# Power.net
KiCad netlist of a schematic drawn in Altium Designer
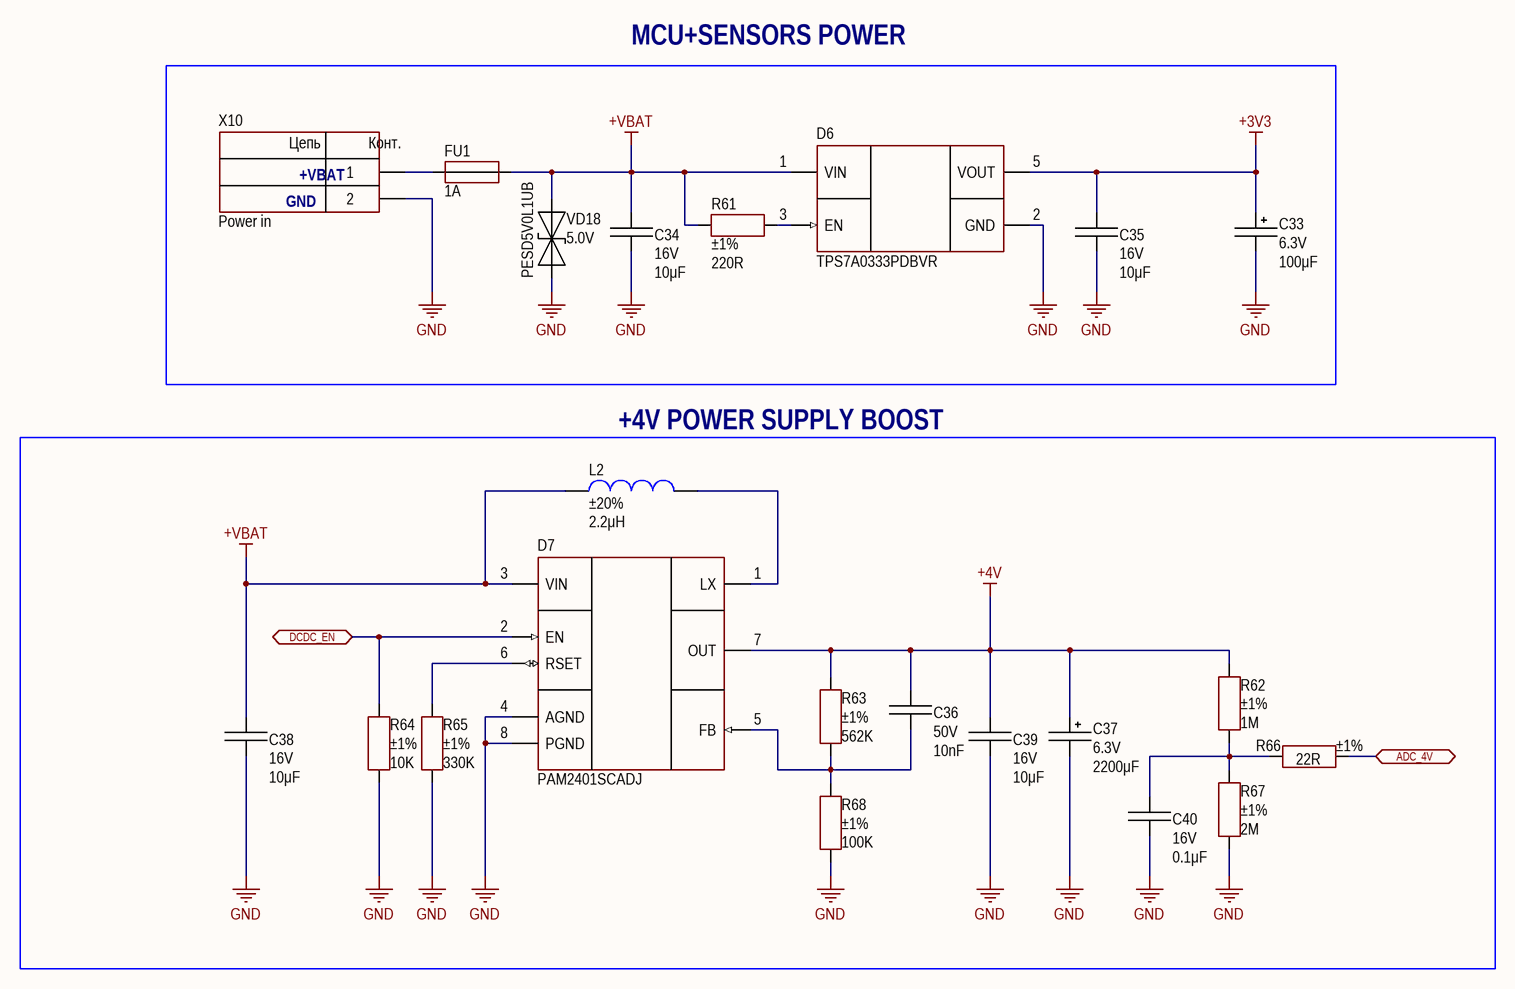
[diagram p0: Power.SchDoc]

(export (version "E")
  (design (tool "Eeschema 10.0.6"))
  (components
    (comp (ref "C33")
      (value "100μF")
      (footprint "CAP: TANTAL-A")
      (description "100 µF Molded Tantalum Polymer Capacitor 6.3 V 1206 (3216 Metric) 100mOhm @ 100kHz")
      (fields
        (field (name "MANUFACTURER") "AVX")
        (field (name "PARTNUMBER") "TCJA107M006R0100")
        (field (name "VOLTAGE") "6.3V")
      )
      (libsource (lib "capacitor") (part "Tantal_A"))
    )
    (comp (ref "C34")
      (value "10μF")
      (footprint "CAP: 0805")
      (description "±20% 16V Ceramic Capacitor X7R 0805 (2012 Metric)")
      (fields
        (field (name "MANUFACTURER") "Yageo")
        (field (name "PARTNUMBER") "CC0805MKX7R7BB106")
        (field (name "VOLTAGE") "16V")
      )
      (libsource (lib "capacitor") (part "Ceramic_0805"))
    )
    (comp (ref "C35")
      (value "10μF")
      (footprint "CAP: 0805")
      (description "±20% 16V Ceramic Capacitor X7R 0805 (2012 Metric)")
      (fields
        (field (name "MANUFACTURER") "Yageo")
        (field (name "PARTNUMBER") "CC0805MKX7R7BB106")
        (field (name "VOLTAGE") "16V")
      )
      (libsource (lib "capacitor") (part "Ceramic_0805"))
    )
    (comp (ref "C36")
      (value "10nF")
      (footprint "CAP: 0402")
      (description "10000 pF ±10% 50V Ceramic Capacitor X7R 0402 (1005 Metric)")
      (fields
        (field (name "MANUFACTURER") "Yageo")
        (field (name "PARTNUMBER") "CC0402KRX7R9BB103")
        (field (name "VOLTAGE") "50V")
      )
      (libsource (lib "capacitor") (part "Ceramic_0402"))
    )
    (comp (ref "C37")
      (value "2200μF")
      (footprint "CAP: D10C5H12.5")
      (description "2200 µF 6.3 V Aluminum - Polymer Capacitors Radial, Can 13mOhm 2000 Hrs @ 125°C")
      (fields
        (field (name "MANUFACTURER") "KEMET")
        (field (name "PARTNUMBER") "A759MS228M0JAAE013")
        (field (name "VOLTAGE") "6.3V")
      )
      (libsource (lib "capacitor") (part "Aluminium"))
    )
    (comp (ref "C38")
      (value "10μF")
      (footprint "CAP: 0805")
      (description "±20% 16V Ceramic Capacitor X7R 0805 (2012 Metric)")
      (fields
        (field (name "MANUFACTURER") "Yageo")
        (field (name "PARTNUMBER") "CC0805MKX7R7BB106")
        (field (name "VOLTAGE") "16V")
      )
      (libsource (lib "capacitor") (part "Ceramic_0805"))
    )
    (comp (ref "C39")
      (value "10μF")
      (footprint "CAP: 0805")
      (description "±20% 16V Ceramic Capacitor X7R 0805 (2012 Metric)")
      (fields
        (field (name "MANUFACTURER") "Yageo")
        (field (name "PARTNUMBER") "CC0805MKX7R7BB106")
        (field (name "VOLTAGE") "16V")
      )
      (libsource (lib "capacitor") (part "Ceramic_0805"))
    )
    (comp (ref "C40")
      (value "0.1μF")
      (footprint "CAP: 0402")
      (description "±10% 16V Ceramic Capacitor X7R 0402 (1005 Metric)")
      (fields
        (field (name "MANUFACTURER") "Yageo")
        (field (name "PARTNUMBER") "CC0402KRX7R7BB104")
        (field (name "VOLTAGE") "16V")
      )
      (libsource (lib "capacitor") (part "Ceramic_0402"))
    )
    (comp (ref "D6")
      (value "~")
      (footprint "SOT23-5")
      (description "Linear Voltage Regulator IC Positive Fixed 1 Output 3.3V 200mA SOT-23-5")
      (fields
        (field (name "MANUFACTURER") "Texas Instruments")
        (field (name "VALUEMANUFACTURERPARTNUMBER") "Linear voltage regulator, input 3.2...6V, 0.27V, output 3.3V, 0.2A, -40...+85°C, SOT23-6")
        (field (name "PARTNUMBER") "TPS7A0333PDBVR")
      )
      (libsource (lib "ic-power-supply") (part "AP2204K-3.3TRG1"))
    )
    (comp (ref "D7")
      (value "~")
      (footprint "8-TSSOP")
      (fields
        (field (name "MANUFACTURER") "Diodes Incorporated")
        (field (name "VALUEMANUFACTURERPARTNUMBER") "DC/DC boost converter, input 0.9...4.75V, 1MHz, output 2.5..5V, 1A, -40...+125°C, TO-263-5")
        (field (name "PARTNUMBER") "PAM2401SCADJ")
      )
      (libsource (lib "MyLib") (part "PAM2401SCADJ"))
    )
    (comp (ref "FU1")
      (value "~")
      (footprint "FUSE: 1206")
      (description "Polymeric PTC Resettable Fuse 6V 1 A Ih Surface Mount 1206 (3216 Metric), Concave")
      (fields
        (field (name "MANUFACTURER") "Bel Fuse Inc.")
        (field (name "VALUEMANUFACTURERPARTNUMBER") "Electromechanics relay, 6V, 1A, 1206, ")
        (field (name "MAXCURRENT") "1A")
      )
      (libsource (lib "electromechanics") (part "Fuse"))
    )
    (comp (ref "L2")
      (value "2.2μH")
      (footprint "IND: 1008 (2520)")
      (description "2.2 µH Shielded Multilayer Inductor 1.3 A 80mOhm Max 1008 (2520 Metric)")
      (fields
        (field (name "MANUFACTURER") "Bourns")
        (field (name "PARTNUMBER") "CVH252009-2R2M")
        (field (name "TOLERANCE") "±20%")
      )
      (libsource (lib "MyLib") (part "Inductor_1008 (2520)"))
    )
    (comp (ref "R61")
      (value "220R")
      (footprint "RES: 0402")
      (description "220 Ohms ±1% 0.063W, 1/16W Chip Resistor 0402 (1005 Metric) Moisture Resistant Thick Film")
      (fields
        (field (name "MANUFACTURER") "Yageo")
        (field (name "PARTNUMBER") "RC0402FR-07220RL")
        (field (name "TOLERANCE") "±1%")
      )
      (libsource (lib "") (part "Resistor_0402_2"))
    )
    (comp (ref "R62")
      (value "1M")
      (footprint "RES: 0402")
      (description "1 MOhms ±1% 0.063W, 1/16W Chip Resistor 0402 (1005 Metric) Moisture Resistant Thick Film")
      (fields
        (field (name "MANUFACTURER") "Yageo")
        (field (name "PARTNUMBER") "RC0402FR-071ML")
        (field (name "TOLERANCE") "±1%")
      )
      (libsource (lib "") (part "Resistor_0402_1"))
    )
    (comp (ref "R63")
      (value "562K")
      (footprint "RES: 0402")
      (description "562 kOhms ±1% 0.063W, 1/16W Chip Resistor 0402 (1005 Metric) Moisture Resistant Thick Film")
      (fields
        (field (name "MANUFACTURER") "Yageo")
        (field (name "PARTNUMBER") "RC0402FR-07562KL")
        (field (name "TOLERANCE") "±1%")
      )
      (libsource (lib "resistor") (part "Resistor_0402"))
    )
    (comp (ref "R64")
      (value "10K")
      (footprint "RES: 0402")
      (description "10 kOhms ±1% 0.063W, 1/16W Chip Resistor 0402 (1005 Metric) Moisture Resistant Thick Film")
      (fields
        (field (name "MANUFACTURER") "Yageo")
        (field (name "PARTNUMBER") "RC0402FR-0710KL")
        (field (name "TOLERANCE") "±1%")
      )
      (libsource (lib "resistor") (part "Resistor_0402"))
    )
    (comp (ref "R65")
      (value "330K")
      (footprint "RES: 0402")
      (description "330 kOhms ±1% 0.063W, 1/16W Chip Resistor 0402 (1005 Metric) Moisture Resistant Thick Film")
      (fields
        (field (name "MANUFACTURER") "Yageo")
        (field (name "PARTNUMBER") "RC0402FR-07330KL")
        (field (name "TOLERANCE") "±1%")
      )
      (libsource (lib "resistor") (part "Resistor_0402"))
    )
    (comp (ref "R66")
      (value "22R")
      (footprint "RES: 0402")
      (description "22 Ohms ±1% 0.063W, 1/16W Chip Resistor 0402 (1005 Metric) Moisture Resistant Thick Film")
      (fields
        (field (name "MANUFACTURER") "Yageo")
        (field (name "PARTNUMBER") "RC0402FR-0722RL")
        (field (name "TOLERANCE") "±1%")
      )
      (libsource (lib "resistor") (part "Resistor_0402"))
    )
    (comp (ref "R67")
      (value "2M")
      (footprint "RES: 0402")
      (description "2 MOhms ±1% 0.063W, 1/16W Chip Resistor 0402 (1005 Metric) Moisture Resistant Thick Film")
      (fields
        (field (name "MANUFACTURER") "Yageo")
        (field (name "PARTNUMBER") "RC0402FR-072ML")
        (field (name "TOLERANCE") "±1%")
      )
      (libsource (lib "") (part "Resistor_0402_1"))
    )
    (comp (ref "R68")
      (value "100K")
      (footprint "RES: 0402")
      (description "100 kOhms ±1% 0.063W, 1/16W Chip Resistor 0402 (1005 Metric) Moisture Resistant Thick Film")
      (fields
        (field (name "MANUFACTURER") "Yageo")
        (field (name "PARTNUMBER") "RC0402FR-07100KL")
        (field (name "TOLERANCE") "±1%")
      )
      (libsource (lib "resistor") (part "Resistor_0402"))
    )
    (comp (ref "VD18")
      (value "~")
      (footprint "DIODE: SOD523")
      (description "12V Clamp 3.5A (8/20µs) Ipp Tvs Diode Surface Mount SOD-523")
      (fields
        (field (name "MANUFACTURER") "Nexperia")
        (field (name "VALUEMANUFACTURERPARTNUMBER") "ESD TVS diode, 5.0V, 3.5A, , , SOD-523, -55...+150°C")
        (field (name "VOLTAGE") "5.0V")
        (field (name "PARTNUMBER") "PESD5V0L1UB")
      )
      (libsource (lib "diode") (part "TVS_single"))
    )
    (comp (ref "X10")
      (value "~")
      (footprint "CON: 282834-2")
      (description "2 Position Wire to Board Terminal Block Horizontal with Board 0.100\" (2.54mm) Through Hole")
      (fields
        (field (name "MANUFACTURER") "KLS")
        (field (name "VALUEMANUFACTURERPARTNUMBER") "Block Terminal, 2pin, , 500VAC, 15A")
        (field (name "COMMENTTEXT") "Power in")
      )
      (libsource (lib "MyLib") (part "KLS2-308V-2.54-02P-4S"))
    )
  )
  (nets
    (net (code "1") (name "+3V3") (class "Default")
      (node (ref "C33") (pin "1") (pinfunction "1_1") (pintype "passive"))
      (node (ref "C35") (pin "2") (pinfunction "2_2") (pintype "passive"))
      (node (ref "D6") (pin "5") (pinfunction "VOUT_5") (pintype "passive"))
    )
    (net (code "2") (name "+4V") (class "Default")
      (node (ref "C36") (pin "2") (pinfunction "2_2") (pintype "passive"))
      (node (ref "C37") (pin "1") (pinfunction "1_1") (pintype "passive"))
      (node (ref "C39") (pin "2") (pinfunction "2_2") (pintype "passive"))
      (node (ref "D7") (pin "7") (pinfunction "OUT_7") (pintype "power_in"))
      (node (ref "R62") (pin "2") (pinfunction "2_2") (pintype "passive"))
      (node (ref "R63") (pin "2") (pinfunction "2_2") (pintype "passive"))
    )
    (net (code "3") (name "+VBAT") (class "Default")
      (node (ref "C34") (pin "2") (pinfunction "2_2") (pintype "passive"))
      (node (ref "C38") (pin "2") (pinfunction "2_2") (pintype "passive"))
      (node (ref "D6") (pin "1") (pinfunction "VIN_1") (pintype "passive"))
      (node (ref "D7") (pin "3") (pinfunction "VIN_3") (pintype "power_in"))
      (node (ref "FU1") (pin "2") (pinfunction "2_2") (pintype "passive"))
      (node (ref "L2") (pin "2") (pinfunction "2_2") (pintype "passive"))
      (node (ref "R61") (pin "2") (pinfunction "2_2") (pintype "passive"))
      (node (ref "VD18") (pin "2") (pinfunction "C_2") (pintype "passive"))
    )
    (net (code "4") (name "/ADC_4V") (class "Default")
      (node (ref "R66") (pin "2") (pinfunction "2_2") (pintype "passive"))
    )
    (net (code "5") (name "/DCDC_EN") (class "Default")
      (node (ref "D7") (pin "2") (pinfunction "EN_2") (pintype "input"))
      (node (ref "R64") (pin "2") (pinfunction "2_2") (pintype "passive"))
    )
    (net (code "6") (name "GND") (class "Default")
      (node (ref "C33") (pin "2") (pinfunction "2_2") (pintype "passive"))
      (node (ref "C34") (pin "1") (pinfunction "1_1") (pintype "passive"))
      (node (ref "C35") (pin "1") (pinfunction "1_1") (pintype "passive"))
      (node (ref "C37") (pin "2") (pinfunction "2_2") (pintype "passive"))
      (node (ref "C38") (pin "1") (pinfunction "1_1") (pintype "passive"))
      (node (ref "C39") (pin "1") (pinfunction "1_1") (pintype "passive"))
      (node (ref "C40") (pin "1") (pinfunction "1_1") (pintype "passive"))
      (node (ref "D6") (pin "2") (pinfunction "GND_2") (pintype "passive"))
      (node (ref "D7") (pin "4") (pinfunction "AGND_4") (pintype "power_in"))
      (node (ref "D7") (pin "8") (pinfunction "PGND_8") (pintype "power_in"))
      (node (ref "R64") (pin "1") (pinfunction "1_1") (pintype "passive"))
      (node (ref "R65") (pin "1") (pinfunction "1_1") (pintype "passive"))
      (node (ref "R67") (pin "1") (pinfunction "1_1") (pintype "passive"))
      (node (ref "R68") (pin "1") (pinfunction "1_1") (pintype "passive"))
      (node (ref "VD18") (pin "1") (pinfunction "A_1") (pintype "passive"))
      (node (ref "X10") (pin "2") (pinfunction "2_2") (pintype "passive"))
    )
    (net (code "7") (name "Net-(C40-Pad2)") (class "Default")
      (node (ref "C40") (pin "2") (pinfunction "2_2") (pintype "passive"))
      (node (ref "R62") (pin "1") (pinfunction "1_1") (pintype "passive"))
      (node (ref "R66") (pin "1") (pinfunction "1_1") (pintype "passive"))
      (node (ref "R67") (pin "2") (pinfunction "2_2") (pintype "passive"))
    )
    (net (code "8") (name "Net-(D6-EN)") (class "Default")
      (node (ref "D6") (pin "3") (pinfunction "EN_3") (pintype "input"))
      (node (ref "R61") (pin "1") (pinfunction "1_1") (pintype "passive"))
    )
    (net (code "9") (name "Net-(D7-FB)") (class "Default")
      (node (ref "C36") (pin "1") (pinfunction "1_1") (pintype "passive"))
      (node (ref "D7") (pin "5") (pinfunction "FB_5") (pintype "input"))
      (node (ref "R63") (pin "1") (pinfunction "1_1") (pintype "passive"))
      (node (ref "R68") (pin "2") (pinfunction "2_2") (pintype "passive"))
    )
    (net (code "10") (name "Net-(D7-LX)") (class "Default")
      (node (ref "D7") (pin "1") (pinfunction "LX_1") (pintype "power_in"))
      (node (ref "L2") (pin "1") (pinfunction "1_1") (pintype "passive"))
    )
    (net (code "11") (name "Net-(D7-RSET)") (class "Default")
      (node (ref "D7") (pin "6") (pinfunction "RSET_6") (pintype "bidirectional"))
      (node (ref "R65") (pin "2") (pinfunction "2_2") (pintype "passive"))
    )
    (net (code "12") (name "Net-(FU1-Pad1)") (class "Default")
      (node (ref "FU1") (pin "1") (pinfunction "1_1") (pintype "passive"))
      (node (ref "X10") (pin "1") (pinfunction "1_1") (pintype "passive"))
    )
  )
)
